# SAMV71_Xplained_Ultra_Power_Converter.net
KiCad netlist of a schematic drawn in Altium Designer
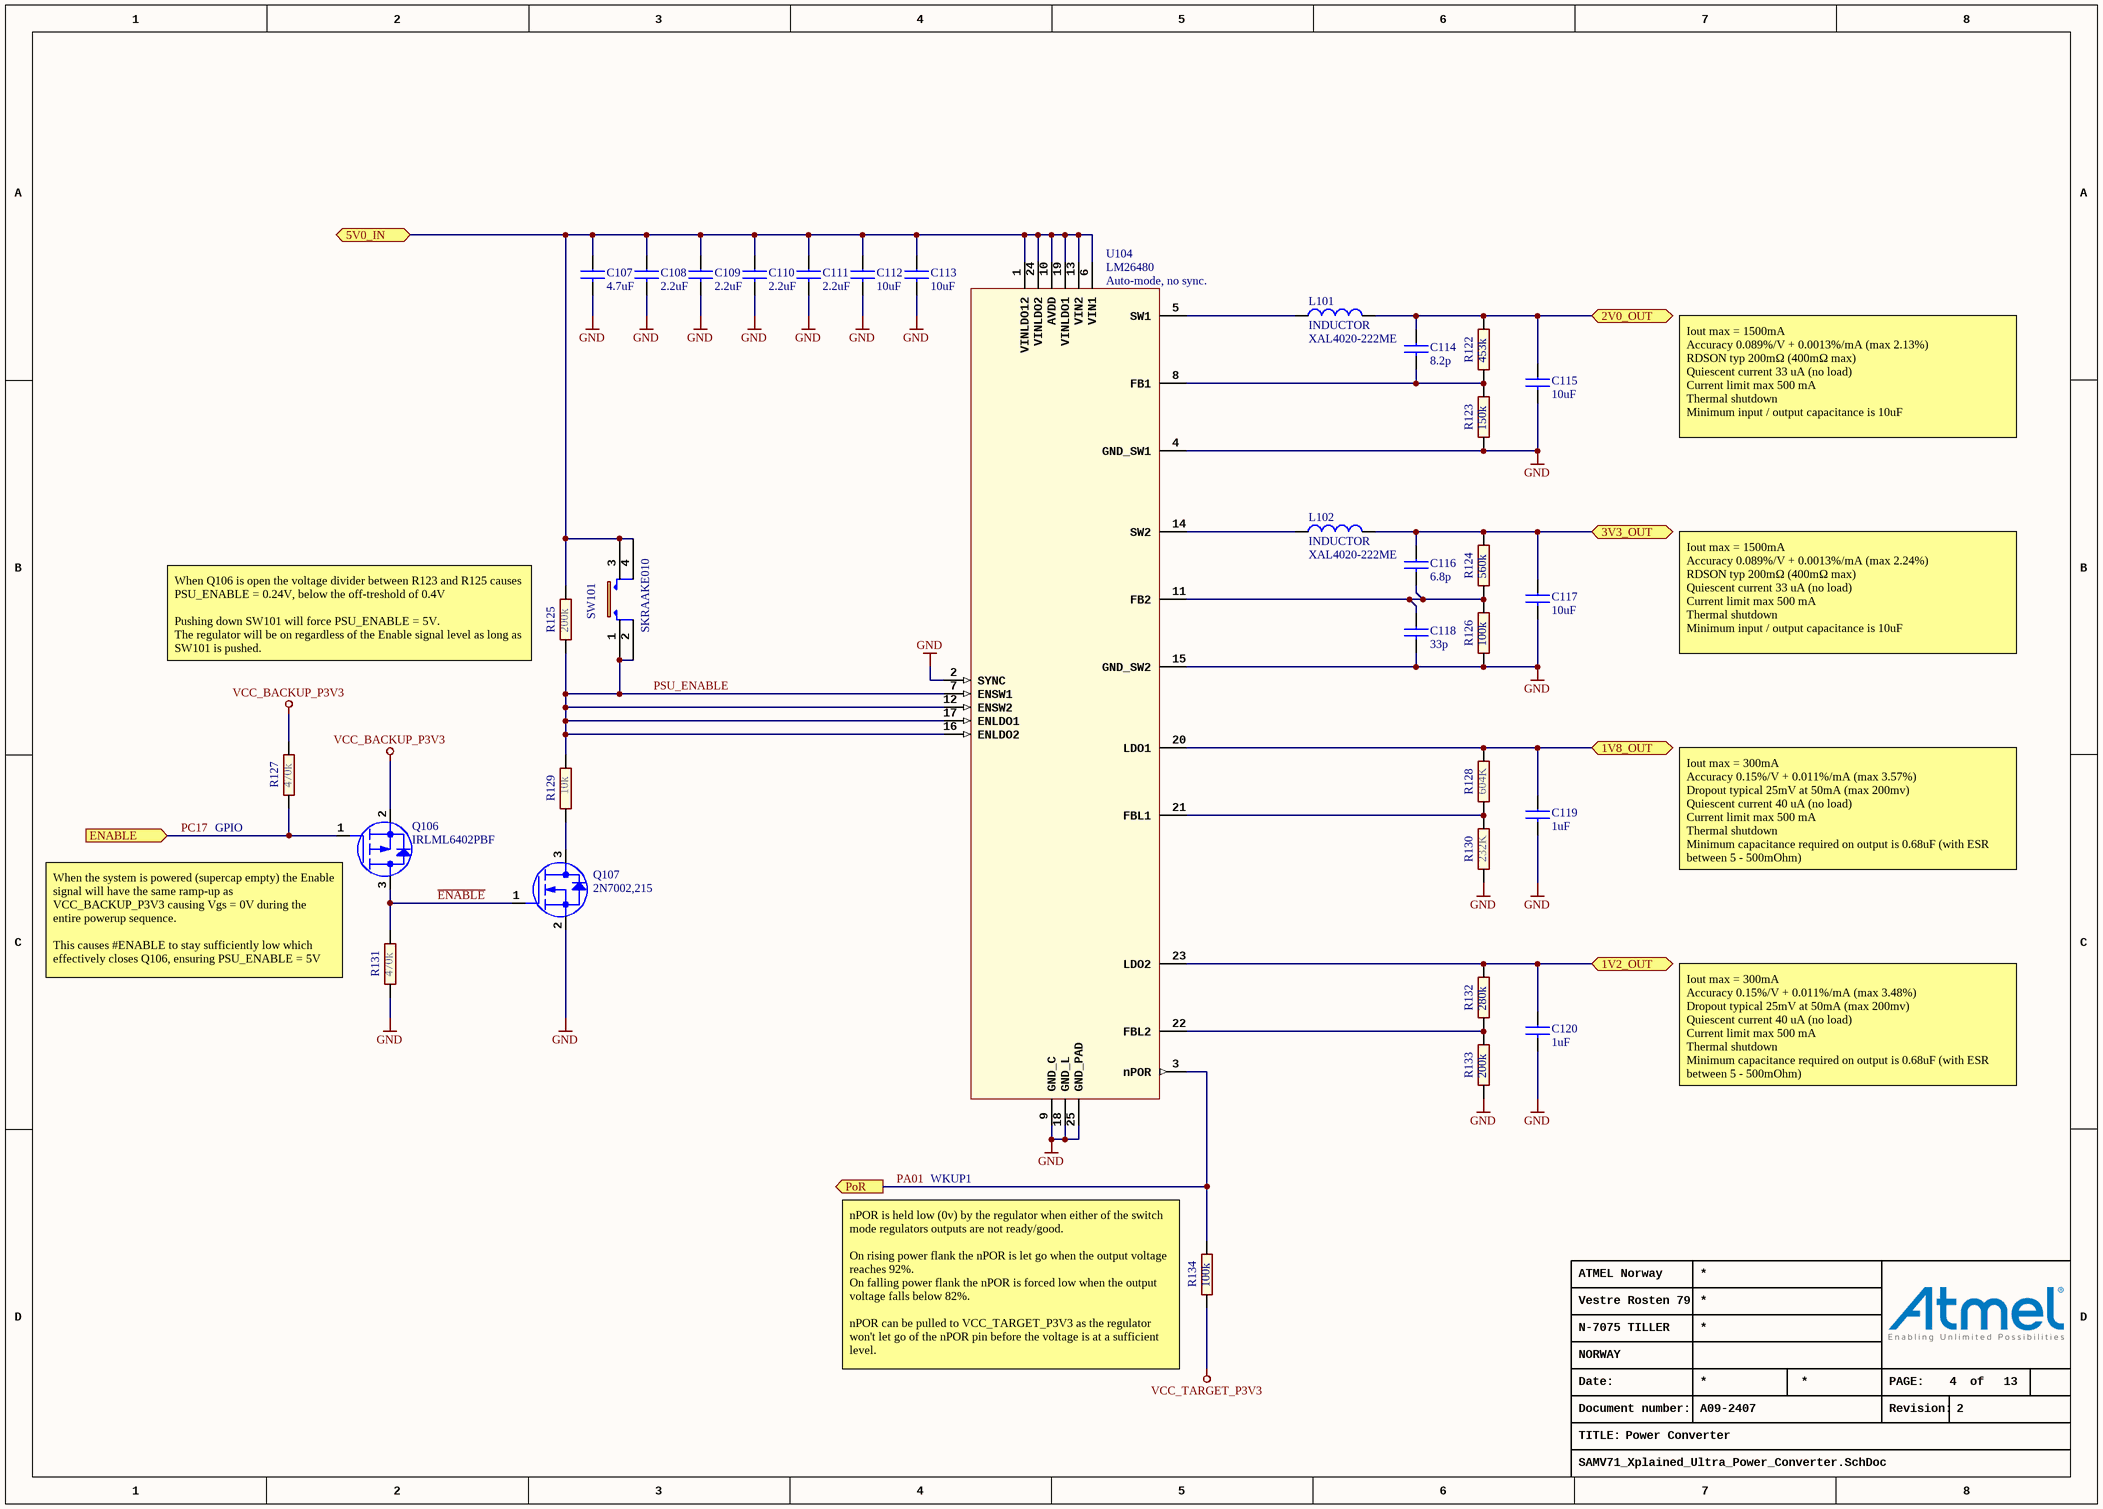
[diagram p0: SAMV71_Xplained_Ultra_Power_Converter.SchDoc]

(export (version "E")
  (design (tool "Eeschema 10.0.6"))
  (components
    (comp (ref "C107")
      (value "4.7uF")
      (footprint "AP1-00039")
      (description "Ceramic capacitor, SMD 0603, X5R, 10V, 10% (de31036)")
      (fields (field (name "TOLERANCE") "10%") (field (name "MANUFACTURER") "tdk"))
      (libsource (lib "AltiumDbLib") (part "CAP-NONPOL"))
    )
    (comp (ref "C108")
      (value "2.2uF")
      (footprint "AP1-00053")
      (description "Ceramic capacitor, SMD 0402, X5R, 6.3V, +/-20%")
      (fields (field (name "TOLERANCE") "Â±20%") (field (name "MANUFACTURER") "Kemet"))
      (libsource (lib "AltiumDbLib") (part "CAP-NONPOL"))
    )
    (comp (ref "C109")
      (value "2.2uF")
      (footprint "AP1-00053")
      (description "Ceramic capacitor, SMD 0402, X5R, 6.3V, +/-20%")
      (fields (field (name "TOLERANCE") "Â±20%") (field (name "MANUFACTURER") "Kemet"))
      (libsource (lib "AltiumDbLib") (part "CAP-NONPOL"))
    )
    (comp (ref "C110")
      (value "2.2uF")
      (footprint "AP1-00053")
      (description "Ceramic capacitor, SMD 0402, X5R, 6.3V, +/-20%")
      (fields (field (name "TOLERANCE") "Â±20%") (field (name "MANUFACTURER") "Kemet"))
      (libsource (lib "AltiumDbLib") (part "CAP-NONPOL"))
    )
    (comp (ref "C111")
      (value "2.2uF")
      (footprint "AP1-00053")
      (description "Ceramic capacitor, SMD 0402, X5R, 6.3V, +/-20%")
      (fields (field (name "TOLERANCE") "Â±20%") (field (name "MANUFACTURER") "Kemet"))
      (libsource (lib "AltiumDbLib") (part "CAP-NONPOL"))
    )
    (comp (ref "C112")
      (value "10uF")
      (footprint "AP1-00041")
      (description "Ceramic capacitor, SMD 0805, X5R, 10V, 10 %, (de19441)")
      (fields (field (name "TOLERANCE") "10%") (field (name "MANUFACTURER") "Murata"))
      (libsource (lib "AltiumDbLib") (part "CAP-NONPOL"))
    )
    (comp (ref "C113")
      (value "10uF")
      (footprint "AP1-00041")
      (description "Ceramic capacitor, SMD 0805, X5R, 10V, 10 %, (de19441)")
      (fields (field (name "TOLERANCE") "10%") (field (name "MANUFACTURER") "Murata"))
      (libsource (lib "AltiumDbLib") (part "CAP-NONPOL"))
    )
    (comp (ref "C114")
      (value "8.2p")
      (footprint "AP1-00053")
      (description "Ceramic capacitor, SMD 0402, NP0, 50V, +/-5%")
      (fields (field (name "TOLERANCE") "50V, +/-5%") (field (name "Comment") "CAP-NONPOL"))
      (libsource (lib "AltiumDbLib") (part "CAP-NONPOL"))
    )
    (comp (ref "C115")
      (value "10uF")
      (footprint "AP1-00041")
      (description "Ceramic capacitor, SMD 0805, X5R, 10V, 10 %, (de19441)")
      (fields (field (name "TOLERANCE") "10%") (field (name "MANUFACTURER") "Murata"))
      (libsource (lib "AltiumDbLib") (part "CAP-NONPOL"))
    )
    (comp (ref "C116")
      (value "6.8p")
      (footprint "AP1-00053")
      (description "Ceramic capacitor, SMD 0402, NP0, 50V, +/-5%")
      (fields (field (name "TOLERANCE") "50V, +/-5%") (field (name "Comment") "CAP-NONPOL"))
      (libsource (lib "AltiumDbLib") (part "CAP-NONPOL"))
    )
    (comp (ref "C117")
      (value "10uF")
      (footprint "AP1-00041")
      (description "Ceramic capacitor, SMD 0805, X5R, 10V, 10 %, (de19441)")
      (fields (field (name "TOLERANCE") "10%") (field (name "MANUFACTURER") "Murata"))
      (libsource (lib "AltiumDbLib") (part "CAP-NONPOL"))
    )
    (comp (ref "C118")
      (value "33p")
      (footprint "AP1-00053")
      (description "Ceramic capacitor, SMD 0402, NP0, 50V, +/-5%")
      (fields (field (name "TOLERANCE") "50V, +/-5%") (field (name "Comment") "CAP-NONPOL"))
      (libsource (lib "AltiumDbLib") (part "CAP-NONPOL"))
    )
    (comp (ref "C119")
      (value "1uF")
      (footprint "AP1-00053")
      (description "Ceramic capacitor, SMD 0402, X5R, 10V, ±10 %")
      (fields (field (name "MANUFACTURER") "AVX") (field (name "MPN") "0402ZD105KAT2A"))
      (libsource (lib "AltiumDbLib") (part "CAP-NONPOL"))
    )
    (comp (ref "C120")
      (value "1uF")
      (footprint "AP1-00053")
      (description "Ceramic capacitor, SMD 0402, X5R, 10V, ±10 %")
      (fields (field (name "MANUFACTURER") "AVX") (field (name "MPN") "0402ZD105KAT2A"))
      (libsource (lib "AltiumDbLib") (part "CAP-NONPOL"))
    )
    (comp (ref "L101")
      (value "INDUCTOR")
      (footprint "AP3-00119")
      (description "2.2ÂµH Shielded Power Inductor, 4x4x2mm, Isat=5.6A , Irms=4.0A , DCR=35.2mÎ©")
      (fields (field (name "ALTIUM_VALUE") "XAL4020-222ME") (field (name "TOLERANCE") "20%"))
      (libsource (lib "AltiumDbLib") (part "INDUCTOR"))
    )
    (comp (ref "L102")
      (value "INDUCTOR")
      (footprint "AP3-00119")
      (description "2.2ÂµH Shielded Power Inductor, 4x4x2mm, Isat=5.6A , Irms=4.0A , DCR=35.2mÎ©")
      (fields (field (name "ALTIUM_VALUE") "XAL4020-222ME") (field (name "TOLERANCE") "20%"))
      (libsource (lib "AltiumDbLib") (part "INDUCTOR"))
    )
    (comp (ref "Q106")
      (value "IRLML6402PBF")
      (footprint "AP5-00002")
      (description "P-ch. MOSFET. -30V, -3.7A continuous,RDS(ON)=0.05Ohm@VGS=-4,5V, RDS(ON)=0.08Ohm@VGS=-2.5V")
      (fields (field (name "MANUFACTURER") "International Rectifier") (field (name "Comment") "MOSFET_P_GSD"))
      (libsource (lib "AltiumDbLib") (part "MOSFET_P_GSD"))
    )
    (comp (ref "Q107")
      (value "2N7002,215")
      (footprint "AP5-00002")
      (description "N-Channel MOSFET. 60V, 0.300A continuous, 1.2A Peak. RDS(ON) = 3.8Ohm@VGS=4.5V, VGS(th)<2.5V")
      (fields (field (name "MANUFACTURER") "NXP") (field (name "Comment") "MOSFET_N_GSD"))
      (libsource (lib "AltiumDbLib") (part "MOSFET_N_GSD"))
    )
    (comp (ref "R122")
      (value "453k")
      (footprint "AP2-00011")
      (description "Thick film resistor, SMD 0402, 1/16W, 1%")
      (fields (field (name "TOLERANCE") "1 %") (field (name "Comment") "R2"))
      (libsource (lib "AltiumDbLib") (part "R2"))
    )
    (comp (ref "R123")
      (value "150k")
      (footprint "AP2-00011")
      (description "Thick film resistor, SMD 0402, 1/16W, 1%")
      (fields (field (name "TOLERANCE") "1 %") (field (name "Comment") "R2"))
      (libsource (lib "AltiumDbLib") (part "R2"))
    )
    (comp (ref "R124")
      (value "560k")
      (footprint "AP2-00011")
      (description "Thick film resistor, SMD 0402, 1/16W, 1%")
      (fields (field (name "TOLERANCE") "1 %") (field (name "Comment") "R2"))
      (libsource (lib "AltiumDbLib") (part "R2"))
    )
    (comp (ref "R125")
      (value "200k")
      (footprint "AP2-00011")
      (description "Thick film resistor, SMD 0402, 1/16W, 1%")
      (fields (field (name "TOLERANCE") "1 %") (field (name "Comment") "R2"))
      (libsource (lib "AltiumDbLib") (part "R2"))
    )
    (comp (ref "R126")
      (value "100k")
      (footprint "AP2-00011")
      (description "Thick film resistor, SMD 0402, 1/16W, 1%")
      (fields (field (name "TOLERANCE") "1 %") (field (name "Comment") "R2"))
      (libsource (lib "") (part "R2_1"))
    )
    (comp (ref "R127")
      (value "470k")
      (footprint "AP2-00011")
      (description "Thick film resistor, SMD 0402, 1/16W, 1%")
      (fields (field (name "TOLERANCE") "1 %") (field (name "Comment") "R2"))
      (libsource (lib "AltiumDbLib") (part "R2"))
    )
    (comp (ref "R128")
      (value "604K")
      (footprint "AP2-00011")
      (description "Thick film resistor, SMD 0402, 1/16W, 1%")
      (fields (field (name "TOLERANCE") "1 %") (field (name "Comment") "R2"))
      (libsource (lib "AltiumDbLib") (part "R2"))
    )
    (comp (ref "R129")
      (value "10k")
      (footprint "AP2-00011")
      (description "Thick film resistor, SMD 0402, 1/16W, 1%")
      (fields (field (name "TOLERANCE") "1 %") (field (name "MANUFACTURER") "vishay"))
      (libsource (lib "AltiumDbLib") (part "R2"))
    )
    (comp (ref "R130")
      (value "232K")
      (footprint "AP2-00011")
      (description "Thick film resistor, SMD 0402, 1/16W, 1%")
      (fields (field (name "TOLERANCE") "1 %") (field (name "Comment") "R2"))
      (libsource (lib "AltiumDbLib") (part "R2"))
    )
    (comp (ref "R131")
      (value "470k")
      (footprint "AP2-00011")
      (description "Thick film resistor, SMD 0402, 1/16W, 1%")
      (fields (field (name "TOLERANCE") "1 %") (field (name "Comment") "R2"))
      (libsource (lib "AltiumDbLib") (part "R2"))
    )
    (comp (ref "R132")
      (value "280k")
      (footprint "AP2-00011")
      (description "Thick film resistor, SMD 0402, 1/16W, 1%")
      (fields (field (name "TOLERANCE") "1 %") (field (name "Comment") "R2"))
      (libsource (lib "AltiumDbLib") (part "R2"))
    )
    (comp (ref "R133")
      (value "200k")
      (footprint "AP2-00011")
      (description "Thick film resistor, SMD 0402, 1/16W, 1%")
      (fields (field (name "TOLERANCE") "1 %") (field (name "Comment") "R2"))
      (libsource (lib "AltiumDbLib") (part "R2"))
    )
    (comp (ref "R134")
      (value "100k")
      (footprint "AP2-00011")
      (description "Thick film resistor, SMD 0402, 1/16W, 1%")
      (fields (field (name "TOLERANCE") "1 %") (field (name "Comment") "R2"))
      (libsource (lib "") (part "R2_1"))
    )
    (comp (ref "SW101")
      (value "SKRAAKE010")
      (footprint "AP8-00137")
      (description "6.2x6.2 mm SMD tact switch, same as A08-0091 but less force is needed")
      (fields
        (field (name "MANUFACTURER") "ALPS")
        (field (name "Comment") "Can be ordered in low volumes from Mouser")
      )
      (libsource (lib "AltiumDbLib") (part "PUSHBUTTON1"))
    )
    (comp (ref "U104")
      (value "Auto-mode, no sync.")
      (footprint "AP6-00380")
      (description "Externally Programmable Dual High-Current Step-Down DC/DC and Dual Linear Regulators")
      (fields (field (name "ALTIUM_VALUE") "LM26480"))
      (libsource (lib "AltiumDbLib") (part "LM26480"))
    )
  )
  (nets
    (net (code "1") (name "/1V2_OUT") (class "Default")
      (node (ref "C120") (pin "1") (pinfunction "1_1") (pintype "passive"))
      (node (ref "R132") (pin "2") (pinfunction "2_2") (pintype "passive"))
      (node (ref "U104") (pin "23") (pinfunction "LDO2_23") (pintype "power_in"))
    )
    (net (code "2") (name "/1V8_OUT") (class "Default")
      (node (ref "C119") (pin "1") (pinfunction "1_1") (pintype "passive"))
      (node (ref "R128") (pin "2") (pinfunction "2_2") (pintype "passive"))
      (node (ref "U104") (pin "20") (pinfunction "LDO1_20") (pintype "power_in"))
    )
    (net (code "3") (name "/2V0_OUT") (class "Default")
      (node (ref "C114") (pin "1") (pinfunction "1_1") (pintype "passive"))
      (node (ref "C115") (pin "1") (pinfunction "1_1") (pintype "passive"))
      (node (ref "L101") (pin "2") (pinfunction "2_2") (pintype "passive"))
      (node (ref "R122") (pin "2") (pinfunction "2_2") (pintype "passive"))
    )
    (net (code "4") (name "/3V3_OUT") (class "Default")
      (node (ref "C116") (pin "1") (pinfunction "1_1") (pintype "passive"))
      (node (ref "C117") (pin "1") (pinfunction "1_1") (pintype "passive"))
      (node (ref "L102") (pin "2") (pinfunction "2_2") (pintype "passive"))
      (node (ref "R124") (pin "2") (pinfunction "2_2") (pintype "passive"))
    )
    (net (code "5") (name "/5V0_IN") (class "Default")
      (node (ref "C107") (pin "1") (pinfunction "1_1") (pintype "passive"))
      (node (ref "C108") (pin "1") (pinfunction "1_1") (pintype "passive"))
      (node (ref "C109") (pin "1") (pinfunction "1_1") (pintype "passive"))
      (node (ref "C110") (pin "1") (pinfunction "1_1") (pintype "passive"))
      (node (ref "C111") (pin "1") (pinfunction "1_1") (pintype "passive"))
      (node (ref "C112") (pin "1") (pinfunction "1_1") (pintype "passive"))
      (node (ref "C113") (pin "1") (pinfunction "1_1") (pintype "passive"))
      (node (ref "R125") (pin "2") (pinfunction "2_2") (pintype "passive"))
      (node (ref "SW101") (pin "3") (pinfunction "3_3") (pintype "passive"))
      (node (ref "SW101") (pin "4") (pinfunction "4_4") (pintype "passive"))
      (node (ref "U104") (pin "1") (pinfunction "VINLDO12_1") (pintype "power_in"))
      (node (ref "U104") (pin "10") (pinfunction "AVDD_10") (pintype "power_in"))
      (node (ref "U104") (pin "13") (pinfunction "VIN2_13") (pintype "power_in"))
      (node (ref "U104") (pin "19") (pinfunction "VINLDO1_19") (pintype "power_in"))
      (node (ref "U104") (pin "24") (pinfunction "VINLDO2_24") (pintype "power_in"))
      (node (ref "U104") (pin "6") (pinfunction "VIN1_6") (pintype "power_in"))
    )
    (net (code "6") (name "/PA01") (class "Default")
      (node (ref "R134") (pin "1") (pinfunction "1_1") (pintype "passive"))
      (node (ref "U104") (pin "3") (pinfunction "nPOR_3") (pintype "output"))
    )
    (net (code "7") (name "/PC17") (class "Default")
      (node (ref "Q106") (pin "1") (pinfunction "G_1") (pintype "passive"))
      (node (ref "R127") (pin "1") (pinfunction "1_1") (pintype "passive"))
    )
    (net (code "8") (name "/PSU_ENABLE") (class "Default")
      (node (ref "R125") (pin "1") (pinfunction "1_1") (pintype "passive"))
      (node (ref "R129") (pin "2") (pinfunction "2_2") (pintype "passive"))
      (node (ref "SW101") (pin "1") (pinfunction "1_1") (pintype "passive"))
      (node (ref "SW101") (pin "2") (pinfunction "2_2") (pintype "passive"))
      (node (ref "U104") (pin "12") (pinfunction "ENSW2_12") (pintype "input"))
      (node (ref "U104") (pin "16") (pinfunction "ENLDO2_16") (pintype "input"))
      (node (ref "U104") (pin "17") (pinfunction "ENLDO1_17") (pintype "input"))
      (node (ref "U104") (pin "7") (pinfunction "ENSW1_7") (pintype "input"))
    )
    (net (code "9") (name "/~{ENABLE}") (class "Default")
      (node (ref "Q106") (pin "3") (pinfunction "D_3") (pintype "passive"))
      (node (ref "Q107") (pin "1") (pinfunction "G_1") (pintype "passive"))
      (node (ref "R131") (pin "2") (pinfunction "2_2") (pintype "passive"))
    )
    (net (code "10") (name "GND") (class "Default")
      (node (ref "C107") (pin "2") (pinfunction "2_2") (pintype "passive"))
      (node (ref "C108") (pin "2") (pinfunction "2_2") (pintype "passive"))
      (node (ref "C109") (pin "2") (pinfunction "2_2") (pintype "passive"))
      (node (ref "C110") (pin "2") (pinfunction "2_2") (pintype "passive"))
      (node (ref "C111") (pin "2") (pinfunction "2_2") (pintype "passive"))
      (node (ref "C112") (pin "2") (pinfunction "2_2") (pintype "passive"))
      (node (ref "C113") (pin "2") (pinfunction "2_2") (pintype "passive"))
      (node (ref "C115") (pin "2") (pinfunction "2_2") (pintype "passive"))
      (node (ref "C117") (pin "2") (pinfunction "2_2") (pintype "passive"))
      (node (ref "C118") (pin "2") (pinfunction "2_2") (pintype "passive"))
      (node (ref "C119") (pin "2") (pinfunction "2_2") (pintype "passive"))
      (node (ref "C120") (pin "2") (pinfunction "2_2") (pintype "passive"))
      (node (ref "Q107") (pin "2") (pinfunction "S_2") (pintype "passive"))
      (node (ref "R123") (pin "1") (pinfunction "1_1") (pintype "passive"))
      (node (ref "R126") (pin "2") (pinfunction "2_2") (pintype "passive"))
      (node (ref "R130") (pin "1") (pinfunction "1_1") (pintype "passive"))
      (node (ref "R131") (pin "1") (pinfunction "1_1") (pintype "passive"))
      (node (ref "R133") (pin "1") (pinfunction "1_1") (pintype "passive"))
      (node (ref "U104") (pin "15") (pinfunction "GND_SW2_15") (pintype "power_in"))
      (node (ref "U104") (pin "18") (pinfunction "GND_L_18") (pintype "power_in"))
      (node (ref "U104") (pin "2") (pinfunction "SYNC_2") (pintype "input"))
      (node (ref "U104") (pin "25") (pinfunction "GND_PAD_25") (pintype "passive"))
      (node (ref "U104") (pin "4") (pinfunction "GND_SW1_4") (pintype "power_in"))
      (node (ref "U104") (pin "9") (pinfunction "GND_C_9") (pintype "power_in"))
    )
    (net (code "11") (name "Net-(Q107-D)") (class "Default")
      (node (ref "Q107") (pin "3") (pinfunction "D_3") (pintype "passive"))
      (node (ref "R129") (pin "1") (pinfunction "1_1") (pintype "passive"))
    )
    (net (code "12") (name "Net-(U104-FB1)") (class "Default")
      (node (ref "C114") (pin "2") (pinfunction "2_2") (pintype "passive"))
      (node (ref "R122") (pin "1") (pinfunction "1_1") (pintype "passive"))
      (node (ref "R123") (pin "2") (pinfunction "2_2") (pintype "passive"))
      (node (ref "U104") (pin "8") (pinfunction "FB1_8") (pintype "power_in"))
    )
    (net (code "13") (name "Net-(U104-FB2)") (class "Default")
      (node (ref "C116") (pin "2") (pinfunction "2_2") (pintype "passive"))
      (node (ref "C118") (pin "1") (pinfunction "1_1") (pintype "passive"))
      (node (ref "R124") (pin "1") (pinfunction "1_1") (pintype "passive"))
      (node (ref "R126") (pin "1") (pinfunction "1_1") (pintype "passive"))
      (node (ref "U104") (pin "11") (pinfunction "FB2_11") (pintype "power_in"))
    )
    (net (code "14") (name "Net-(U104-FBL1)") (class "Default")
      (node (ref "R128") (pin "1") (pinfunction "1_1") (pintype "passive"))
      (node (ref "R130") (pin "2") (pinfunction "2_2") (pintype "passive"))
      (node (ref "U104") (pin "21") (pinfunction "FBL1_21") (pintype "power_in"))
    )
    (net (code "15") (name "Net-(U104-FBL2)") (class "Default")
      (node (ref "R132") (pin "1") (pinfunction "1_1") (pintype "passive"))
      (node (ref "R133") (pin "2") (pinfunction "2_2") (pintype "passive"))
      (node (ref "U104") (pin "22") (pinfunction "FBL2_22") (pintype "power_in"))
    )
    (net (code "16") (name "Net-(U104-SW1)") (class "Default")
      (node (ref "L101") (pin "1") (pinfunction "1_1") (pintype "passive"))
      (node (ref "U104") (pin "5") (pinfunction "SW1_5") (pintype "power_in"))
    )
    (net (code "17") (name "Net-(U104-SW2)") (class "Default")
      (node (ref "L102") (pin "1") (pinfunction "1_1") (pintype "passive"))
      (node (ref "U104") (pin "14") (pinfunction "SW2_14") (pintype "power_in"))
    )
    (net (code "18") (name "VCC_BACKUP_P3V3") (class "Default")
      (node (ref "Q106") (pin "2") (pinfunction "S_2") (pintype "passive"))
      (node (ref "R127") (pin "2") (pinfunction "2_2") (pintype "passive"))
    )
    (net (code "19") (name "VCC_TARGET_P3V3") (class "Default")
      (node (ref "R134") (pin "2") (pinfunction "2_2") (pintype "passive"))
    )
  )
)
